# twip-mb2.net
KiCad netlist of a schematic drawn in EAGLE
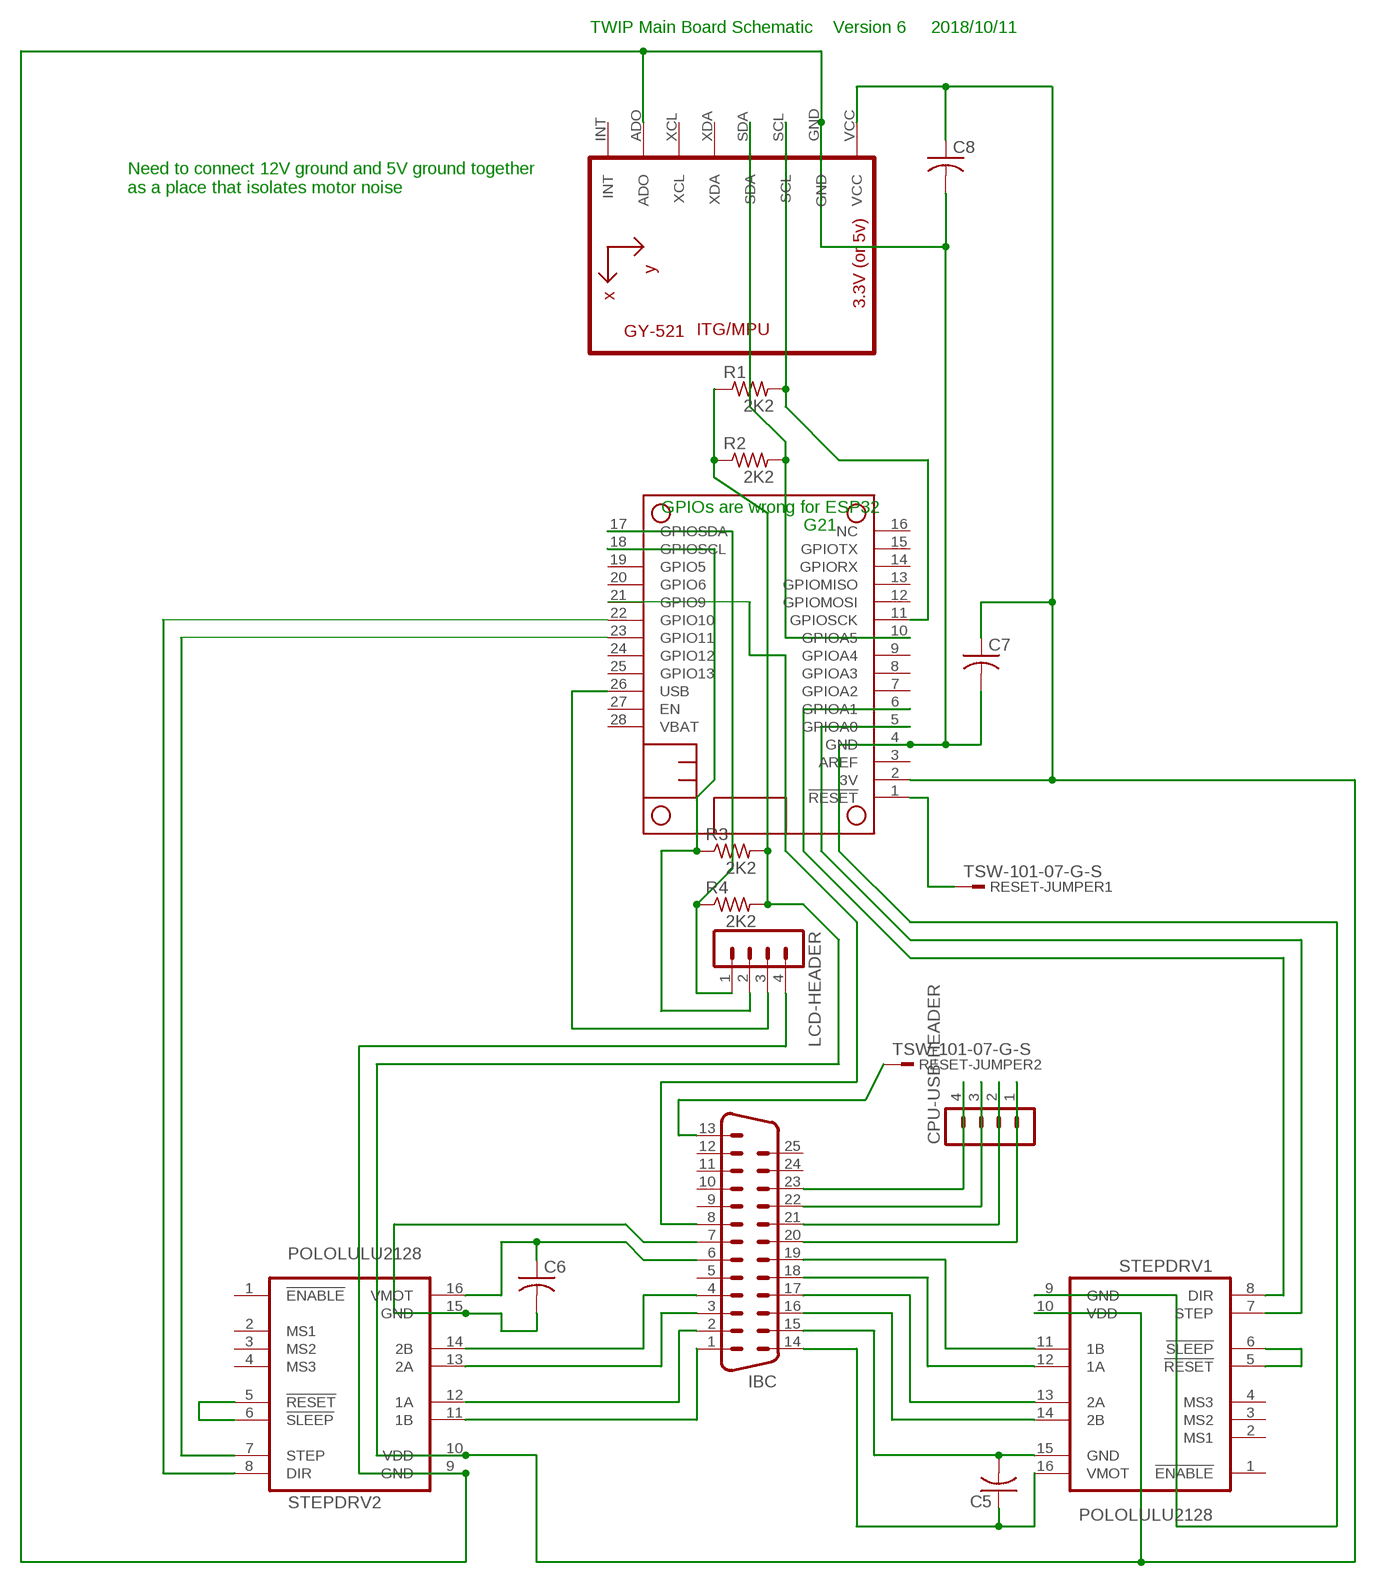
[diagram p0: schematic, sheet 1]

(export (version "E")
  (design (tool "Eeschema 10.0.6"))
  (components
    (comp (ref "C5")
      (value "C-US050-024X044")
      (footprint "eagle-import:C050-024X044")
      (libsource (lib "eagle-import") (part "C-US050-024X044"))
    )
    (comp (ref "C6")
      (value "C-US050-024X044")
      (footprint "eagle-import:C050-024X044")
      (libsource (lib "eagle-import") (part "C-US050-024X044"))
    )
    (comp (ref "C7")
      (value "C-US050-024X044")
      (footprint "eagle-import:C050-024X044")
      (libsource (lib "eagle-import") (part "C-US050-024X044"))
    )
    (comp (ref "C8")
      (value "C-US050-024X044")
      (footprint "eagle-import:C050-024X044")
      (libsource (lib "eagle-import") (part "C-US050-024X044"))
    )
    (comp (ref "CPU-USB-HEADER")
      (value "MA04-1")
      (footprint "eagle-import:MA04-1")
      (libsource (lib "eagle-import") (part "MA04-1"))
    )
    (comp (ref "IBC")
      (value "M25VP")
      (footprint "eagle-import:M25VP")
      (libsource (lib "eagle-import") (part "M25VP"))
    )
    (comp (ref "LCD-HEADER")
      (value "MA04-1")
      (footprint "eagle-import:MA04-1")
      (libsource (lib "eagle-import") (part "MA04-1"))
    )
    (comp (ref "MS2")
      (value "FEATHERWING_NOHOLES")
      (footprint "eagle-import:FEATHERWING_NOHOLES")
      (libsource (lib "eagle-import") (part "FEATHERWING_NOHOLES"))
    )
    (comp (ref "R1")
      (value "2K2")
      (footprint "eagle-import:0309_12")
      (libsource (lib "eagle-import") (part "R-US_0309/12"))
    )
    (comp (ref "R2")
      (value "2K2")
      (footprint "eagle-import:0309_12")
      (libsource (lib "eagle-import") (part "R-US_0309/12"))
    )
    (comp (ref "R3")
      (value "2K2")
      (footprint "eagle-import:0309_12")
      (libsource (lib "eagle-import") (part "R-US_0309/12"))
    )
    (comp (ref "R4")
      (value "2K2")
      (footprint "eagle-import:0309_12")
      (libsource (lib "eagle-import") (part "R-US_0309/12"))
    )
    (comp (ref "RESET-JUMPER1")
      (value "TSW-101-07-G-S")
      (footprint "eagle-import:TSW-101-XX-G-S")
      (fields (field (name "MF") "Samtec Inc."))
      (libsource (lib "eagle-import") (part "TSW-101--G-S07"))
    )
    (comp (ref "RESET-JUMPER2")
      (value "TSW-101-07-G-S")
      (footprint "eagle-import:TSW-101-XX-G-S")
      (fields (field (name "MF") "Samtec Inc."))
      (libsource (lib "eagle-import") (part "TSW-101--G-S07"))
    )
    (comp (ref "STEPDRV1")
      (value "POLOLULU2128")
      (footprint "eagle-import:POLOLULU2128")
      (libsource (lib "eagle-import") (part "POLOLULU2128"))
    )
    (comp (ref "STEPDRV2")
      (value "POLOLULU2128")
      (footprint "eagle-import:POLOLULU2128")
      (libsource (lib "eagle-import") (part "POLOLULU2128"))
    )
    (comp (ref "U1")
      (value "GY-521MPU6050")
      (footprint "eagle-import:GY-521")
      (libsource (lib "eagle-import") (part "GY-521MPU6050"))
    )
  )
  (nets
    (net (code "1") (name "/VBAT") (class "Default")
      (node (ref "MS2") (pin "28") (pinfunction "VBAT_28") (pintype "power_in"))
    )
    (net (code "2") (name "Net-(C5-Pad2)") (class "Default")
      (node (ref "C5") (pin "2") (pinfunction "2_2") (pintype "passive"))
      (node (ref "IBC") (pin "15") (pinfunction "15_15") (pintype "passive"))
      (node (ref "STEPDRV1") (pin "15") (pinfunction "GND_15") (pintype "power_in"))
    )
    (net (code "3") (name "Net-(C6-Pad2)") (class "Default")
      (node (ref "C6") (pin "2") (pinfunction "2_2") (pintype "passive"))
      (node (ref "IBC") (pin "7") (pinfunction "7_7") (pintype "passive"))
      (node (ref "STEPDRV2") (pin "15") (pinfunction "GND_15") (pintype "power_in"))
    )
    (net (code "4") (name "Net-(CPU-USB-HEADER-Pad1)") (class "Default")
      (node (ref "CPU-USB-HEADER") (pin "1") (pinfunction "1_1") (pintype "passive"))
      (node (ref "IBC") (pin "20") (pinfunction "20_20") (pintype "passive"))
    )
    (net (code "5") (name "Net-(CPU-USB-HEADER-Pad2)") (class "Default")
      (node (ref "CPU-USB-HEADER") (pin "2") (pinfunction "2_2") (pintype "passive"))
      (node (ref "IBC") (pin "21") (pinfunction "21_21") (pintype "passive"))
    )
    (net (code "6") (name "Net-(CPU-USB-HEADER-Pad3)") (class "Default")
      (node (ref "CPU-USB-HEADER") (pin "3") (pinfunction "3_3") (pintype "passive"))
      (node (ref "IBC") (pin "22") (pinfunction "22_22") (pintype "passive"))
    )
    (net (code "7") (name "Net-(CPU-USB-HEADER-Pad4)") (class "Default")
      (node (ref "CPU-USB-HEADER") (pin "4") (pinfunction "4_4") (pintype "passive"))
      (node (ref "IBC") (pin "23") (pinfunction "23_23") (pintype "passive"))
    )
    (net (code "8") (name "Net-(IBC-Pad13)") (class "Default")
      (node (ref "IBC") (pin "13") (pinfunction "13_13") (pintype "passive"))
      (node (ref "RESET-JUMPER2") (pin "1") (pinfunction "1_1") (pintype "passive"))
    )
    (net (code "9") (name "Net-(MS2-3V)") (class "Default")
      (node (ref "C7") (pin "1") (pinfunction "1_1") (pintype "passive"))
      (node (ref "C8") (pin "1") (pinfunction "1_1") (pintype "passive"))
      (node (ref "MS2") (pin "2") (pinfunction "3V_2") (pintype "power_in"))
      (node (ref "R1") (pin "1") (pinfunction "1_1") (pintype "passive"))
      (node (ref "R2") (pin "1") (pinfunction "1_1") (pintype "passive"))
      (node (ref "R3") (pin "2") (pinfunction "2_2") (pintype "passive"))
      (node (ref "R4") (pin "2") (pinfunction "2_2") (pintype "passive"))
      (node (ref "STEPDRV1") (pin "10") (pinfunction "VDD_10") (pintype "power_in"))
      (node (ref "STEPDRV2") (pin "10") (pinfunction "VDD_10") (pintype "power_in"))
      (node (ref "U1") (pin "VCC") (pinfunction "VCC_VCC") (pintype "bidirectional"))
    )
    (net (code "10") (name "Net-(MS2-GND)") (class "Default")
      (node (ref "C7") (pin "2") (pinfunction "2_2") (pintype "passive"))
      (node (ref "C8") (pin "2") (pinfunction "2_2") (pintype "passive"))
      (node (ref "LCD-HEADER") (pin "4") (pinfunction "4_4") (pintype "passive"))
      (node (ref "MS2") (pin "4") (pinfunction "GND_4") (pintype "power_in"))
      (node (ref "STEPDRV1") (pin "9") (pinfunction "GND_9") (pintype "power_in"))
      (node (ref "STEPDRV2") (pin "9") (pinfunction "GND_9") (pintype "power_in"))
      (node (ref "U1") (pin "ADO") (pinfunction "ADO_ADO") (pintype "bidirectional"))
      (node (ref "U1") (pin "GND") (pinfunction "GND_GND") (pintype "bidirectional"))
    )
    (net (code "11") (name "Net-(MS2-GPIO9)") (class "Default")
      (node (ref "IBC") (pin "8") (pinfunction "8_8") (pintype "passive"))
      (node (ref "MS2") (pin "21") (pinfunction "GPIO9_21") (pintype "bidirectional"))
    )
    (net (code "12") (name "Net-(MS2-GPIO10)") (class "Default")
      (node (ref "MS2") (pin "22") (pinfunction "GPIO10_22") (pintype "bidirectional"))
      (node (ref "STEPDRV2") (pin "8") (pinfunction "DIR_8") (pintype "input"))
    )
    (net (code "13") (name "Net-(MS2-GPIO11)") (class "Default")
      (node (ref "MS2") (pin "23") (pinfunction "GPIO11_23") (pintype "bidirectional"))
      (node (ref "STEPDRV2") (pin "7") (pinfunction "STEP_7") (pintype "input"))
    )
    (net (code "14") (name "Net-(MS2-GPIOA0)") (class "Default")
      (node (ref "MS2") (pin "5") (pinfunction "GPIOA0_5") (pintype "bidirectional"))
      (node (ref "STEPDRV1") (pin "7") (pinfunction "STEP_7") (pintype "input"))
    )
    (net (code "15") (name "Net-(MS2-GPIOA1)") (class "Default")
      (node (ref "MS2") (pin "6") (pinfunction "GPIOA1_6") (pintype "bidirectional"))
      (node (ref "STEPDRV1") (pin "8") (pinfunction "DIR_8") (pintype "input"))
    )
    (net (code "16") (name "Net-(MS2-GPIOA5)") (class "Default")
      (node (ref "MS2") (pin "10") (pinfunction "GPIOA5_10") (pintype "bidirectional"))
      (node (ref "R2") (pin "2") (pinfunction "2_2") (pintype "passive"))
      (node (ref "U1") (pin "SDA") (pinfunction "SDA_SDA") (pintype "bidirectional"))
    )
    (net (code "17") (name "Net-(MS2-GPIOSCK)") (class "Default")
      (node (ref "MS2") (pin "11") (pinfunction "GPIOSCK_11") (pintype "bidirectional"))
      (node (ref "R1") (pin "2") (pinfunction "2_2") (pintype "passive"))
      (node (ref "U1") (pin "SCL") (pinfunction "SCL_SCL") (pintype "bidirectional"))
    )
    (net (code "18") (name "Net-(MS2-GPIOSCL)") (class "Default")
      (node (ref "LCD-HEADER") (pin "2") (pinfunction "2_2") (pintype "passive"))
      (node (ref "MS2") (pin "18") (pinfunction "GPIOSCL_18") (pintype "bidirectional"))
      (node (ref "R3") (pin "1") (pinfunction "1_1") (pintype "passive"))
    )
    (net (code "19") (name "Net-(MS2-GPIOSDA)") (class "Default")
      (node (ref "LCD-HEADER") (pin "1") (pinfunction "1_1") (pintype "passive"))
      (node (ref "MS2") (pin "17") (pinfunction "GPIOSDA_17") (pintype "bidirectional"))
      (node (ref "R4") (pin "1") (pinfunction "1_1") (pintype "passive"))
    )
    (net (code "20") (name "Net-(MS2-USB)") (class "Default")
      (node (ref "LCD-HEADER") (pin "3") (pinfunction "3_3") (pintype "passive"))
      (node (ref "MS2") (pin "26") (pinfunction "USB_26") (pintype "power_in"))
    )
    (net (code "21") (name "Net-(MS2-~{RESET})") (class "Default")
      (node (ref "MS2") (pin "1") (pinfunction "~{RESET}_1") (pintype "input"))
      (node (ref "RESET-JUMPER1") (pin "1") (pinfunction "1_1") (pintype "passive"))
    )
    (net (code "22") (name "Net-(STEPDRV1-1A)") (class "Default")
      (node (ref "IBC") (pin "18") (pinfunction "18_18") (pintype "passive"))
      (node (ref "STEPDRV1") (pin "12") (pinfunction "1A_12") (pintype "output"))
    )
    (net (code "23") (name "Net-(STEPDRV1-1B)") (class "Default")
      (node (ref "IBC") (pin "19") (pinfunction "19_19") (pintype "passive"))
      (node (ref "STEPDRV1") (pin "11") (pinfunction "1B_11") (pintype "output"))
    )
    (net (code "24") (name "Net-(STEPDRV1-2A)") (class "Default")
      (node (ref "IBC") (pin "17") (pinfunction "17_17") (pintype "passive"))
      (node (ref "STEPDRV1") (pin "13") (pinfunction "2A_13") (pintype "output"))
    )
    (net (code "25") (name "Net-(STEPDRV1-2B)") (class "Default")
      (node (ref "IBC") (pin "16") (pinfunction "16_16") (pintype "passive"))
      (node (ref "STEPDRV1") (pin "14") (pinfunction "2B_14") (pintype "output"))
    )
    (net (code "26") (name "Net-(STEPDRV1-VMOT)") (class "Default")
      (node (ref "C5") (pin "1") (pinfunction "1_1") (pintype "passive"))
      (node (ref "IBC") (pin "14") (pinfunction "14_14") (pintype "passive"))
      (node (ref "STEPDRV1") (pin "16") (pinfunction "VMOT_16") (pintype "power_in"))
    )
    (net (code "27") (name "Net-(STEPDRV1-~{RESET})") (class "Default")
      (node (ref "STEPDRV1") (pin "5") (pinfunction "~{RESET}_5") (pintype "input"))
      (node (ref "STEPDRV1") (pin "6") (pinfunction "~{SLEEP}_6") (pintype "input"))
    )
    (net (code "28") (name "Net-(STEPDRV2-1A)") (class "Default")
      (node (ref "IBC") (pin "2") (pinfunction "2_2") (pintype "passive"))
      (node (ref "STEPDRV2") (pin "12") (pinfunction "1A_12") (pintype "output"))
    )
    (net (code "29") (name "Net-(STEPDRV2-1B)") (class "Default")
      (node (ref "IBC") (pin "1") (pinfunction "1_1") (pintype "passive"))
      (node (ref "STEPDRV2") (pin "11") (pinfunction "1B_11") (pintype "output"))
    )
    (net (code "30") (name "Net-(STEPDRV2-2A)") (class "Default")
      (node (ref "IBC") (pin "3") (pinfunction "3_3") (pintype "passive"))
      (node (ref "STEPDRV2") (pin "13") (pinfunction "2A_13") (pintype "output"))
    )
    (net (code "31") (name "Net-(STEPDRV2-2B)") (class "Default")
      (node (ref "IBC") (pin "4") (pinfunction "4_4") (pintype "passive"))
      (node (ref "STEPDRV2") (pin "14") (pinfunction "2B_14") (pintype "output"))
    )
    (net (code "32") (name "Net-(STEPDRV2-VMOT)") (class "Default")
      (node (ref "C6") (pin "1") (pinfunction "1_1") (pintype "passive"))
      (node (ref "IBC") (pin "6") (pinfunction "6_6") (pintype "passive"))
      (node (ref "STEPDRV2") (pin "16") (pinfunction "VMOT_16") (pintype "power_in"))
    )
    (net (code "33") (name "Net-(STEPDRV2-~{RESET})") (class "Default")
      (node (ref "STEPDRV2") (pin "5") (pinfunction "~{RESET}_5") (pintype "input"))
      (node (ref "STEPDRV2") (pin "6") (pinfunction "~{SLEEP}_6") (pintype "input"))
    )
    (net (code "34") (name "unconnected-(IBC-Pad5)") (class "Default")
      (node (ref "IBC") (pin "5") (pinfunction "5_5") (pintype "passive"))
    )
    (net (code "35") (name "unconnected-(IBC-Pad9)") (class "Default")
      (node (ref "IBC") (pin "9") (pinfunction "9_9") (pintype "passive"))
    )
    (net (code "36") (name "unconnected-(IBC-Pad10)") (class "Default")
      (node (ref "IBC") (pin "10") (pinfunction "10_10") (pintype "passive"))
    )
    (net (code "37") (name "unconnected-(IBC-Pad11)") (class "Default")
      (node (ref "IBC") (pin "11") (pinfunction "11_11") (pintype "passive"))
    )
    (net (code "38") (name "unconnected-(IBC-Pad12)") (class "Default")
      (node (ref "IBC") (pin "12") (pinfunction "12_12") (pintype "passive"))
    )
    (net (code "39") (name "unconnected-(IBC-Pad24)") (class "Default")
      (node (ref "IBC") (pin "24") (pinfunction "24_24") (pintype "passive"))
    )
    (net (code "40") (name "unconnected-(IBC-Pad25)") (class "Default")
      (node (ref "IBC") (pin "25") (pinfunction "25_25") (pintype "passive"))
    )
    (net (code "41") (name "unconnected-(MS2-AREF-Pad3)") (class "Default")
      (node (ref "MS2") (pin "3") (pinfunction "AREF_3") (pintype "passive"))
    )
    (net (code "42") (name "unconnected-(MS2-EN-Pad27)") (class "Default")
      (node (ref "MS2") (pin "27") (pinfunction "EN_27") (pintype "passive"))
    )
    (net (code "43") (name "unconnected-(MS2-GPIO5-Pad19)") (class "Default")
      (node (ref "MS2") (pin "19") (pinfunction "GPIO5_19") (pintype "bidirectional"))
    )
    (net (code "44") (name "unconnected-(MS2-GPIO6-Pad20)") (class "Default")
      (node (ref "MS2") (pin "20") (pinfunction "GPIO6_20") (pintype "bidirectional"))
    )
    (net (code "45") (name "unconnected-(MS2-GPIO12-Pad24)") (class "Default")
      (node (ref "MS2") (pin "24") (pinfunction "GPIO12_24") (pintype "bidirectional"))
    )
    (net (code "46") (name "unconnected-(MS2-GPIO13-Pad25)") (class "Default")
      (node (ref "MS2") (pin "25") (pinfunction "GPIO13_25") (pintype "bidirectional"))
    )
    (net (code "47") (name "unconnected-(MS2-GPIOA2-Pad7)") (class "Default")
      (node (ref "MS2") (pin "7") (pinfunction "GPIOA2_7") (pintype "bidirectional"))
    )
    (net (code "48") (name "unconnected-(MS2-GPIOA3-Pad8)") (class "Default")
      (node (ref "MS2") (pin "8") (pinfunction "GPIOA3_8") (pintype "bidirectional"))
    )
    (net (code "49") (name "unconnected-(MS2-GPIOA4-Pad9)") (class "Default")
      (node (ref "MS2") (pin "9") (pinfunction "GPIOA4_9") (pintype "bidirectional"))
    )
    (net (code "50") (name "unconnected-(MS2-GPIOMISO-Pad13)") (class "Default")
      (node (ref "MS2") (pin "13") (pinfunction "GPIOMISO_13") (pintype "bidirectional"))
    )
    (net (code "51") (name "unconnected-(MS2-GPIOMOSI-Pad12)") (class "Default")
      (node (ref "MS2") (pin "12") (pinfunction "GPIOMOSI_12") (pintype "bidirectional"))
    )
    (net (code "52") (name "unconnected-(MS2-GPIORX-Pad14)") (class "Default")
      (node (ref "MS2") (pin "14") (pinfunction "GPIORX_14") (pintype "bidirectional"))
    )
    (net (code "53") (name "unconnected-(MS2-GPIOTX-Pad15)") (class "Default")
      (node (ref "MS2") (pin "15") (pinfunction "GPIOTX_15") (pintype "bidirectional"))
    )
    (net (code "54") (name "unconnected-(MS2-NC-Pad16)") (class "Default")
      (node (ref "MS2") (pin "16") (pinfunction "NC_16") (pintype "passive"))
    )
    (net (code "55") (name "unconnected-(STEPDRV1-MS1-Pad2)") (class "Default")
      (node (ref "STEPDRV1") (pin "2") (pinfunction "MS1_2") (pintype "input"))
    )
    (net (code "56") (name "unconnected-(STEPDRV1-MS2-Pad3)") (class "Default")
      (node (ref "STEPDRV1") (pin "3") (pinfunction "MS2_3") (pintype "input"))
    )
    (net (code "57") (name "unconnected-(STEPDRV1-MS3-Pad4)") (class "Default")
      (node (ref "STEPDRV1") (pin "4") (pinfunction "MS3_4") (pintype "input"))
    )
    (net (code "58") (name "unconnected-(STEPDRV1-~{ENABLE}-Pad1)") (class "Default")
      (node (ref "STEPDRV1") (pin "1") (pinfunction "~{ENABLE}_1") (pintype "input"))
    )
    (net (code "59") (name "unconnected-(STEPDRV2-MS1-Pad2)") (class "Default")
      (node (ref "STEPDRV2") (pin "2") (pinfunction "MS1_2") (pintype "input"))
    )
    (net (code "60") (name "unconnected-(STEPDRV2-MS2-Pad3)") (class "Default")
      (node (ref "STEPDRV2") (pin "3") (pinfunction "MS2_3") (pintype "input"))
    )
    (net (code "61") (name "unconnected-(STEPDRV2-MS3-Pad4)") (class "Default")
      (node (ref "STEPDRV2") (pin "4") (pinfunction "MS3_4") (pintype "input"))
    )
    (net (code "62") (name "unconnected-(STEPDRV2-~{ENABLE}-Pad1)") (class "Default")
      (node (ref "STEPDRV2") (pin "1") (pinfunction "~{ENABLE}_1") (pintype "input"))
    )
    (net (code "63") (name "unconnected-(U1-PadINT)") (class "Default")
      (node (ref "U1") (pin "INT") (pinfunction "INT_INT") (pintype "bidirectional"))
    )
    (net (code "64") (name "unconnected-(U1-PadXCL)") (class "Default")
      (node (ref "U1") (pin "XCL") (pinfunction "XCL_XCL") (pintype "bidirectional"))
    )
    (net (code "65") (name "unconnected-(U1-PadXDA)") (class "Default")
      (node (ref "U1") (pin "XDA") (pinfunction "XDA_XDA") (pintype "bidirectional"))
    )
  )
)
